# pico.net
KiCad netlist of a schematic drawn in EAGLE
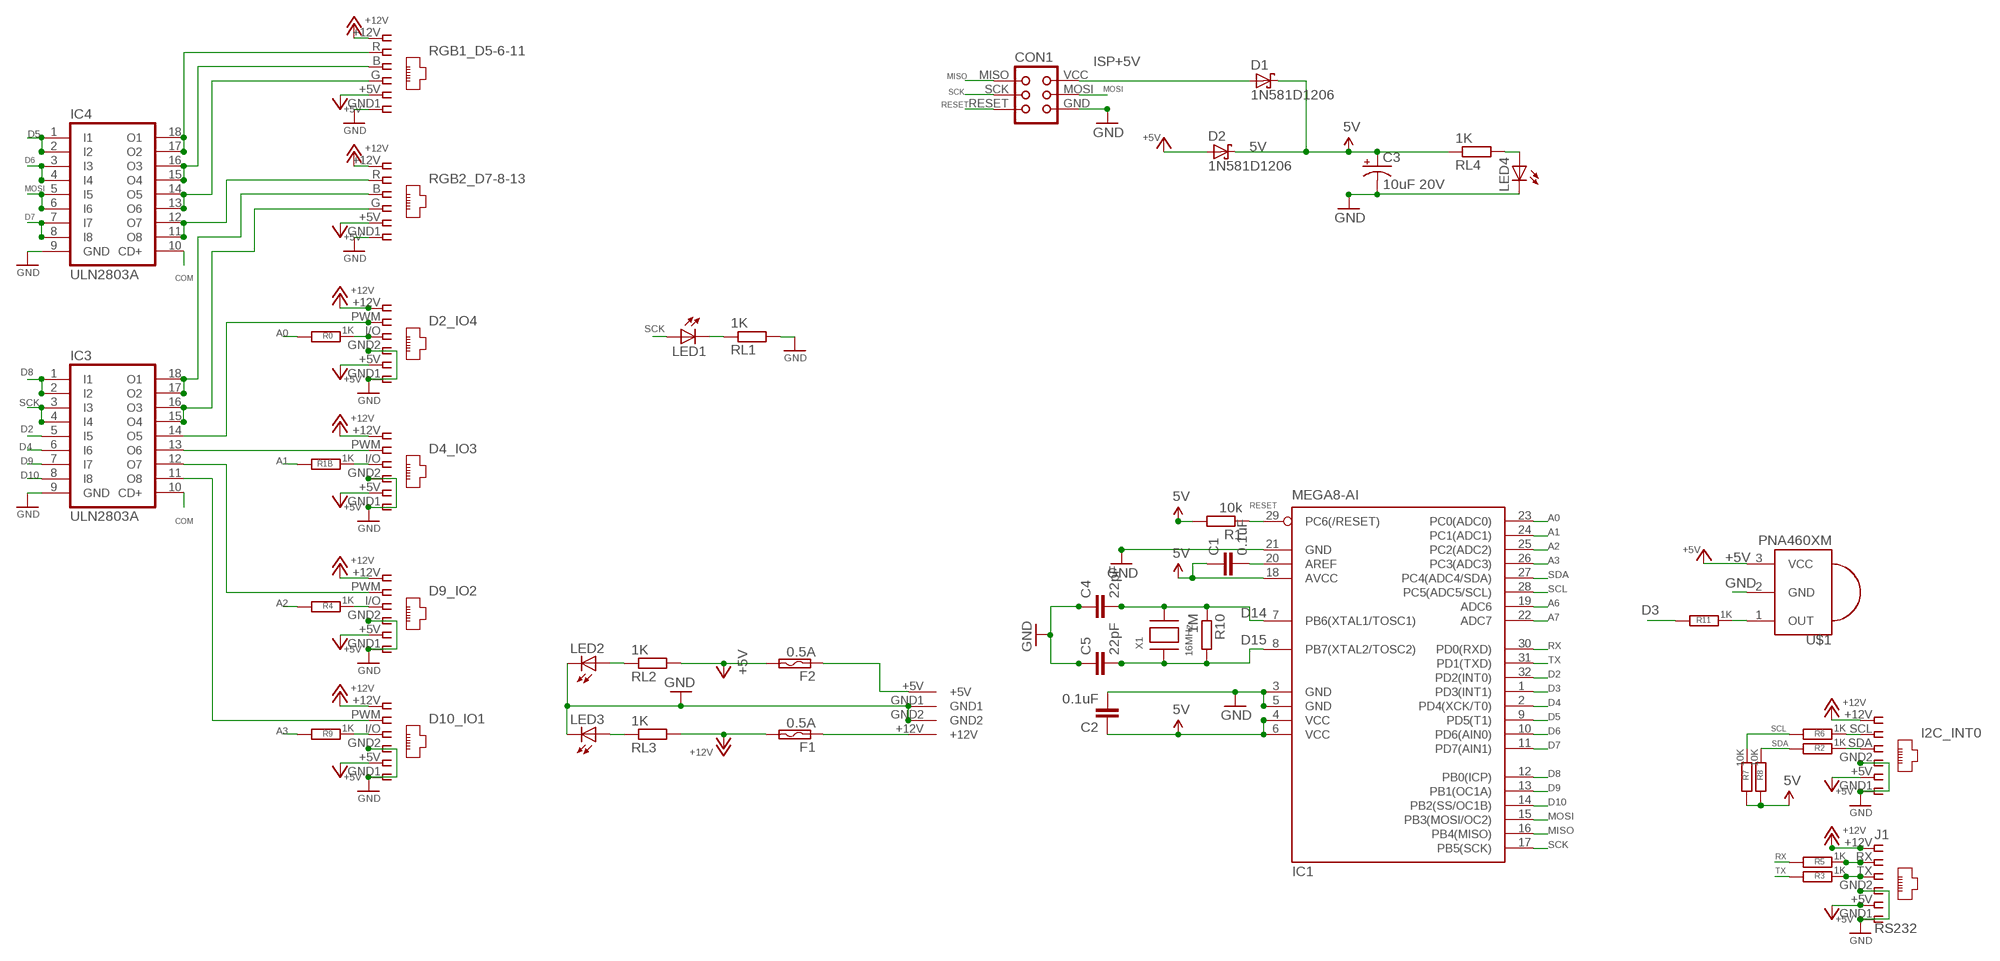
[diagram p0: schematic, sheet 1]

(export (version "E")
  (design (tool "Eeschema 10.0.6"))
  (components
    (comp (ref "C1")
      (value "0.1uF")
      (footprint "eagle-import:C1206")
      (libsource (lib "eagle-import") (part "C-EUC1206"))
    )
    (comp (ref "C2")
      (value "0.1uF")
      (footprint "eagle-import:C1206")
      (libsource (lib "eagle-import") (part "C-EUC1206"))
    )
    (comp (ref "C3")
      (value "10uF 20V")
      (footprint "eagle-import:EIA3216-KIT")
      (libsource (lib "eagle-import") (part "CAP_POL1206-KIT"))
    )
    (comp (ref "C4")
      (value "22pF")
      (footprint "eagle-import:C1206")
      (libsource (lib "eagle-import") (part "C-EUC1206"))
    )
    (comp (ref "C5")
      (value "22pF")
      (footprint "eagle-import:C1206")
      (libsource (lib "eagle-import") (part "C-EUC1206"))
    )
    (comp (ref "CON1")
      (value "TINYISP")
      (footprint "eagle-import:TINYISP")
      (libsource (lib "eagle-import") (part "TINYISP"))
    )
    (comp (ref "D1")
      (value "1N581D1206")
      (footprint "eagle-import:LED-1206")
      (libsource (lib "eagle-import") (part "1N581D1206"))
    )
    (comp (ref "D2")
      (value "1N581D1206")
      (footprint "eagle-import:LED-1206")
      (libsource (lib "eagle-import") (part "1N581D1206"))
    )
    (comp (ref "D2_IO4")
      (value "IO4")
      (footprint "eagle-import:RJ12-STRAIGHT")
      (libsource (lib "eagle-import") (part "RJ12STRAIGHT"))
    )
    (comp (ref "D4_IO3")
      (value "IO3")
      (footprint "eagle-import:RJ12-STRAIGHT")
      (libsource (lib "eagle-import") (part "RJ12STRAIGHT"))
    )
    (comp (ref "D9_IO2")
      (value "IO2")
      (footprint "eagle-import:RJ12-STRAIGHT")
      (libsource (lib "eagle-import") (part "RJ12STRAIGHT"))
    )
    (comp (ref "D10_IO1")
      (value "IO1")
      (footprint "eagle-import:RJ12-STRAIGHT")
      (libsource (lib "eagle-import") (part "RJ12STRAIGHT"))
    )
    (comp (ref "F1")
      (value "0.5A")
      (footprint "eagle-import:C1812")
      (libsource (lib "eagle-import") (part "POLYSWITCHSMD1812"))
    )
    (comp (ref "F2")
      (value "0.5A")
      (footprint "eagle-import:C1812")
      (libsource (lib "eagle-import") (part "POLYSWITCHSMD1812"))
    )
    (comp (ref "I2C_INT0")
      (value "I2C")
      (footprint "eagle-import:RJ12-STRAIGHT-I2C")
      (libsource (lib "eagle-import") (part "RJ12STRAIGHT-I2C"))
    )
    (comp (ref "IC1")
      (value "MEGA8-AI")
      (footprint "eagle-import:TQFP32-08")
      (fields (field (name "MPN") "ATMEGA8-16AU"))
      (libsource (lib "eagle-import") (part "MEGA8-AI"))
    )
    (comp (ref "IC3")
      (value "ULN2803A")
      (footprint "eagle-import:SO18W")
      (libsource (lib "eagle-import") (part "ULN2803A"))
    )
    (comp (ref "IC4")
      (value "ULN2803A")
      (footprint "eagle-import:SO18W")
      (libsource (lib "eagle-import") (part "ULN2803A"))
    )
    (comp (ref "J1")
      (value "RS232")
      (footprint "eagle-import:RJ12-STRAIGHT-RS232")
      (libsource (lib "eagle-import") (part "RJ12STRAIGHT-RS232-SERVER"))
    )
    (comp (ref "LED1")
      (value "LED3MM")
      (footprint "eagle-import:LED3MM")
      (libsource (lib "eagle-import") (part "LED3MM"))
    )
    (comp (ref "LED2")
      (value "LED3MM")
      (footprint "eagle-import:LED3MM")
      (libsource (lib "eagle-import") (part "LED3MM"))
    )
    (comp (ref "LED3")
      (value "LED3MM")
      (footprint "eagle-import:LED3MM")
      (libsource (lib "eagle-import") (part "LED3MM"))
    )
    (comp (ref "LED4")
      (value "LED3MM")
      (footprint "eagle-import:LED3MM")
      (libsource (lib "eagle-import") (part "LED3MM"))
    )
    (comp (ref "R0")
      (value "1K")
      (footprint "eagle-import:M1206")
      (libsource (lib "eagle-import") (part "R-EU_M1206"))
    )
    (comp (ref "R1")
      (value "10k")
      (footprint "eagle-import:M1206")
      (libsource (lib "eagle-import") (part "R-EU_M1206"))
    )
    (comp (ref "R1B")
      (value "1K")
      (footprint "eagle-import:M1206")
      (libsource (lib "eagle-import") (part "R-EU_M1206"))
    )
    (comp (ref "R2")
      (value "1K")
      (footprint "eagle-import:M1206")
      (libsource (lib "eagle-import") (part "R-EU_M1206"))
    )
    (comp (ref "R3")
      (value "1K")
      (footprint "eagle-import:M1206")
      (libsource (lib "eagle-import") (part "R-EU_M1206"))
    )
    (comp (ref "R4")
      (value "1K")
      (footprint "eagle-import:M1206")
      (libsource (lib "eagle-import") (part "R-EU_M1206"))
    )
    (comp (ref "R5")
      (value "1K")
      (footprint "eagle-import:M1206")
      (libsource (lib "eagle-import") (part "R-EU_M1206"))
    )
    (comp (ref "R6")
      (value "1K")
      (footprint "eagle-import:M1206")
      (libsource (lib "eagle-import") (part "R-EU_M1206"))
    )
    (comp (ref "R7")
      (value "10K")
      (footprint "eagle-import:M1206")
      (libsource (lib "eagle-import") (part "R-EU_M1206"))
    )
    (comp (ref "R8")
      (value "10K")
      (footprint "eagle-import:M1206")
      (libsource (lib "eagle-import") (part "R-EU_M1206"))
    )
    (comp (ref "R9")
      (value "1K")
      (footprint "eagle-import:M1206")
      (libsource (lib "eagle-import") (part "R-EU_M1206"))
    )
    (comp (ref "R10")
      (value "1M")
      (footprint "eagle-import:M1206")
      (libsource (lib "eagle-import") (part "R-EU_M1206"))
    )
    (comp (ref "R11")
      (value "1K")
      (footprint "eagle-import:M1206")
      (libsource (lib "eagle-import") (part "R-EU_M1206"))
    )
    (comp (ref "RGB1_D5-6-11")
      (value "RGB1")
      (footprint "eagle-import:RJ12-STRAIGHT-RGB")
      (libsource (lib "eagle-import") (part "RJ12STRAIGHT-RGB"))
    )
    (comp (ref "RGB2_D7-8-13")
      (value "RGB2")
      (footprint "eagle-import:RJ12-STRAIGHT-RGB")
      (libsource (lib "eagle-import") (part "RJ12STRAIGHT-RGB"))
    )
    (comp (ref "RL1")
      (value "1K")
      (footprint "eagle-import:M1206")
      (libsource (lib "eagle-import") (part "R-EU_M1206"))
    )
    (comp (ref "RL2")
      (value "1K")
      (footprint "eagle-import:M1206")
      (libsource (lib "eagle-import") (part "R-EU_M1206"))
    )
    (comp (ref "RL3")
      (value "1K")
      (footprint "eagle-import:M1206")
      (libsource (lib "eagle-import") (part "R-EU_M1206"))
    )
    (comp (ref "RL4")
      (value "1K")
      (footprint "eagle-import:M1206")
      (libsource (lib "eagle-import") (part "R-EU_M1206"))
    )
    (comp (ref "U$1")
      (value "PNA460XM")
      (footprint "eagle-import:PNA460XM")
      (libsource (lib "eagle-import") (part "PNA460XM"))
    )
    (comp (ref "U$2")
      (value "KPJX-4S-S")
      (footprint "eagle-import:KPJX-4S-S")
      (libsource (lib "eagle-import") (part "KPJX-4S-S"))
    )
    (comp (ref "X1")
      (value "16MHz")
      (footprint "eagle-import:NX6035")
      (libsource (lib "eagle-import") (part "XTALNX6035"))
    )
  )
  (nets
    (net (code "1") (name "+5V") (class "Default")
      (node (ref "D10_IO1") (pin "+5V") (pinfunction "5_+5V") (pintype "power_in"))
      (node (ref "D2") (pin "A") (pinfunction "A_A") (pintype "passive"))
      (node (ref "D2_IO4") (pin "+5V") (pinfunction "5_+5V") (pintype "power_in"))
      (node (ref "D4_IO3") (pin "+5V") (pinfunction "5_+5V") (pintype "power_in"))
      (node (ref "D9_IO2") (pin "+5V") (pinfunction "5_+5V") (pintype "power_in"))
      (node (ref "F2") (pin "2") (pinfunction "2_2") (pintype "passive"))
      (node (ref "I2C_INT0") (pin "+5V") (pinfunction "5_+5V") (pintype "power_in"))
      (node (ref "J1") (pin "+5V") (pinfunction "5_+5V") (pintype "power_in"))
      (node (ref "RGB1_D5-6-11") (pin "+5V") (pinfunction "5_+5V") (pintype "power_in"))
      (node (ref "RGB2_D7-8-13") (pin "+5V") (pinfunction "5_+5V") (pintype "power_in"))
      (node (ref "RL2") (pin "2") (pinfunction "2_2") (pintype "passive"))
      (node (ref "U$1") (pin "3") (pinfunction "VCC_3") (pintype "power_in"))
    )
    (net (code "2") (name "+12V") (class "Default")
      (node (ref "D10_IO1") (pin "+12V") (pinfunction "1_+12V") (pintype "power_in"))
      (node (ref "D2_IO4") (pin "+12V") (pinfunction "1_+12V") (pintype "power_in"))
      (node (ref "D4_IO3") (pin "+12V") (pinfunction "1_+12V") (pintype "power_in"))
      (node (ref "D9_IO2") (pin "+12V") (pinfunction "1_+12V") (pintype "power_in"))
      (node (ref "F1") (pin "2") (pinfunction "2_2") (pintype "passive"))
      (node (ref "I2C_INT0") (pin "+12V") (pinfunction "1_+12V") (pintype "power_in"))
      (node (ref "J1") (pin "+12V") (pinfunction "1_+12V") (pintype "power_in"))
      (node (ref "RGB1_D5-6-11") (pin "+12V") (pinfunction "1_+12V") (pintype "power_in"))
      (node (ref "RGB2_D7-8-13") (pin "+12V") (pinfunction "1_+12V") (pintype "power_in"))
      (node (ref "RL3") (pin "2") (pinfunction "2_2") (pintype "passive"))
    )
    (net (code "3") (name "/A0") (class "Default")
      (node (ref "IC1") (pin "23") (pinfunction "PC0(ADC0)_23") (pintype "bidirectional"))
      (node (ref "R0") (pin "2") (pinfunction "2_2") (pintype "passive"))
    )
    (net (code "4") (name "/A1") (class "Default")
      (node (ref "IC1") (pin "24") (pinfunction "PC1(ADC1)_24") (pintype "bidirectional"))
      (node (ref "R1B") (pin "2") (pinfunction "2_2") (pintype "passive"))
    )
    (net (code "5") (name "/A2") (class "Default")
      (node (ref "IC1") (pin "25") (pinfunction "PC2(ADC2)_25") (pintype "bidirectional"))
      (node (ref "R4") (pin "2") (pinfunction "2_2") (pintype "passive"))
    )
    (net (code "6") (name "/A3") (class "Default")
      (node (ref "IC1") (pin "26") (pinfunction "PC3(ADC3)_26") (pintype "bidirectional"))
      (node (ref "R9") (pin "2") (pinfunction "2_2") (pintype "passive"))
    )
    (net (code "7") (name "/A6") (class "Default")
      (node (ref "IC1") (pin "19") (pinfunction "ADC6_19") (pintype "bidirectional"))
    )
    (net (code "8") (name "/A7") (class "Default")
      (node (ref "IC1") (pin "22") (pinfunction "ADC7_22") (pintype "bidirectional"))
    )
    (net (code "9") (name "/COM") (class "Default")
      (node (ref "IC3") (pin "10") (pinfunction "CD+_10") (pintype "passive"))
      (node (ref "IC4") (pin "10") (pinfunction "CD+_10") (pintype "passive"))
    )
    (net (code "10") (name "/D2") (class "Default")
      (node (ref "IC1") (pin "32") (pinfunction "PD2(INT0)_32") (pintype "bidirectional"))
      (node (ref "IC3") (pin "5") (pinfunction "I5_5") (pintype "input"))
    )
    (net (code "11") (name "/D3") (class "Default")
      (node (ref "IC1") (pin "1") (pinfunction "PD3(INT1)_1") (pintype "bidirectional"))
      (node (ref "R11") (pin "2") (pinfunction "2_2") (pintype "passive"))
    )
    (net (code "12") (name "/D4") (class "Default")
      (node (ref "IC1") (pin "2") (pinfunction "PD4(XCK/T0)_2") (pintype "bidirectional"))
      (node (ref "IC3") (pin "6") (pinfunction "I6_6") (pintype "input"))
    )
    (net (code "13") (name "/D5") (class "Default")
      (node (ref "IC1") (pin "9") (pinfunction "PD5(T1)_9") (pintype "bidirectional"))
      (node (ref "IC4") (pin "1") (pinfunction "I1_1") (pintype "input"))
      (node (ref "IC4") (pin "2") (pinfunction "I2_2") (pintype "input"))
    )
    (net (code "14") (name "/D6") (class "Default")
      (node (ref "IC1") (pin "10") (pinfunction "PD6(AIN0)_10") (pintype "bidirectional"))
      (node (ref "IC4") (pin "3") (pinfunction "I3_3") (pintype "input"))
      (node (ref "IC4") (pin "4") (pinfunction "I4_4") (pintype "input"))
    )
    (net (code "15") (name "/D7") (class "Default")
      (node (ref "IC1") (pin "11") (pinfunction "PD7(AIN1)_11") (pintype "bidirectional"))
      (node (ref "IC4") (pin "7") (pinfunction "I7_7") (pintype "input"))
      (node (ref "IC4") (pin "8") (pinfunction "I8_8") (pintype "input"))
    )
    (net (code "16") (name "/D8") (class "Default")
      (node (ref "IC1") (pin "12") (pinfunction "PB0(ICP)_12") (pintype "bidirectional"))
      (node (ref "IC3") (pin "1") (pinfunction "I1_1") (pintype "input"))
      (node (ref "IC3") (pin "2") (pinfunction "I2_2") (pintype "input"))
    )
    (net (code "17") (name "/D9") (class "Default")
      (node (ref "IC1") (pin "13") (pinfunction "PB1(OC1A)_13") (pintype "bidirectional"))
      (node (ref "IC3") (pin "7") (pinfunction "I7_7") (pintype "input"))
    )
    (net (code "18") (name "/D10") (class "Default")
      (node (ref "IC1") (pin "14") (pinfunction "PB2(SS/OC1B)_14") (pintype "bidirectional"))
      (node (ref "IC3") (pin "8") (pinfunction "I8_8") (pintype "input"))
    )
    (net (code "19") (name "/D14") (class "Default")
      (node (ref "C4") (pin "2") (pinfunction "2_2") (pintype "passive"))
      (node (ref "IC1") (pin "7") (pinfunction "PB6(XTAL1/TOSC1)_7") (pintype "bidirectional"))
      (node (ref "R10") (pin "1") (pinfunction "1_1") (pintype "passive"))
      (node (ref "X1") (pin "P$2") (pinfunction "P$2_P$2") (pintype "bidirectional"))
    )
    (net (code "20") (name "/D15") (class "Default")
      (node (ref "C5") (pin "2") (pinfunction "2_2") (pintype "passive"))
      (node (ref "IC1") (pin "8") (pinfunction "PB7(XTAL2/TOSC2)_8") (pintype "bidirectional"))
      (node (ref "R10") (pin "2") (pinfunction "2_2") (pintype "passive"))
      (node (ref "X1") (pin "P$1") (pinfunction "P$1_P$1") (pintype "bidirectional"))
    )
    (net (code "21") (name "/ISP+5V") (class "Default")
      (node (ref "CON1") (pin "VCC") (pinfunction "VCC_VCC") (pintype "passive"))
      (node (ref "D1") (pin "A") (pinfunction "A_A") (pintype "passive"))
    )
    (net (code "22") (name "/MISO") (class "Default")
      (node (ref "CON1") (pin "MISO") (pinfunction "MISO_MISO") (pintype "passive"))
      (node (ref "IC1") (pin "16") (pinfunction "PB4(MISO)_16") (pintype "bidirectional"))
    )
    (net (code "23") (name "/MOSI") (class "Default")
      (node (ref "CON1") (pin "MOSI") (pinfunction "MOSI_MOSI") (pintype "passive"))
      (node (ref "IC1") (pin "15") (pinfunction "PB3(MOSI/OC2)_15") (pintype "bidirectional"))
      (node (ref "IC4") (pin "5") (pinfunction "I5_5") (pintype "input"))
      (node (ref "IC4") (pin "6") (pinfunction "I6_6") (pintype "input"))
    )
    (net (code "24") (name "/RESET") (class "Default")
      (node (ref "CON1") (pin "RESET") (pinfunction "RESET_RESET") (pintype "passive"))
      (node (ref "IC1") (pin "29") (pinfunction "PC6(/RESET)_29") (pintype "bidirectional"))
      (node (ref "R1") (pin "1") (pinfunction "1_1") (pintype "passive"))
    )
    (net (code "25") (name "/RX") (class "Default")
      (node (ref "IC1") (pin "30") (pinfunction "PD0(RXD)_30") (pintype "bidirectional"))
      (node (ref "R5") (pin "2") (pinfunction "2_2") (pintype "passive"))
    )
    (net (code "26") (name "/SCK") (class "Default")
      (node (ref "CON1") (pin "SCK") (pinfunction "SCK_SCK") (pintype "passive"))
      (node (ref "IC1") (pin "17") (pinfunction "PB5(SCK)_17") (pintype "bidirectional"))
      (node (ref "IC3") (pin "3") (pinfunction "I3_3") (pintype "input"))
      (node (ref "IC3") (pin "4") (pinfunction "I4_4") (pintype "input"))
      (node (ref "LED1") (pin "A") (pinfunction "A_A") (pintype "passive"))
    )
    (net (code "27") (name "/SCL") (class "Default")
      (node (ref "IC1") (pin "28") (pinfunction "PC5(ADC5/SCL)_28") (pintype "bidirectional"))
      (node (ref "R6") (pin "2") (pinfunction "2_2") (pintype "passive"))
      (node (ref "R7") (pin "1") (pinfunction "1_1") (pintype "passive"))
    )
    (net (code "28") (name "/SDA") (class "Default")
      (node (ref "IC1") (pin "27") (pinfunction "PC4(ADC4/SDA)_27") (pintype "bidirectional"))
      (node (ref "R2") (pin "2") (pinfunction "2_2") (pintype "passive"))
      (node (ref "R8") (pin "1") (pinfunction "1_1") (pintype "passive"))
    )
    (net (code "29") (name "/TX") (class "Default")
      (node (ref "IC1") (pin "31") (pinfunction "PD1(TXD)_31") (pintype "bidirectional"))
      (node (ref "R3") (pin "2") (pinfunction "2_2") (pintype "passive"))
    )
    (net (code "30") (name "5V") (class "Default")
      (node (ref "C1") (pin "1") (pinfunction "1_1") (pintype "passive"))
      (node (ref "C2") (pin "1") (pinfunction "1_1") (pintype "passive"))
      (node (ref "C3") (pin "A") (pinfunction "+_A") (pintype "passive"))
      (node (ref "D1") (pin "C") (pinfunction "C_C") (pintype "passive"))
      (node (ref "D2") (pin "C") (pinfunction "C_C") (pintype "passive"))
      (node (ref "IC1") (pin "18") (pinfunction "AVCC_18") (pintype "power_in"))
      (node (ref "IC1") (pin "4") (pinfunction "VCC_4") (pintype "power_in"))
      (node (ref "IC1") (pin "6") (pinfunction "VCC_6") (pintype "power_in"))
      (node (ref "R1") (pin "2") (pinfunction "2_2") (pintype "passive"))
      (node (ref "R7") (pin "2") (pinfunction "2_2") (pintype "passive"))
      (node (ref "R8") (pin "2") (pinfunction "2_2") (pintype "passive"))
      (node (ref "RL4") (pin "1") (pinfunction "1_1") (pintype "passive"))
    )
    (net (code "31") (name "GND") (class "Default")
      (node (ref "C2") (pin "2") (pinfunction "2_2") (pintype "passive"))
      (node (ref "C3") (pin "C") (pinfunction "-_C") (pintype "passive"))
      (node (ref "C4") (pin "1") (pinfunction "1_1") (pintype "passive"))
      (node (ref "C5") (pin "1") (pinfunction "1_1") (pintype "passive"))
      (node (ref "CON1") (pin "GND") (pinfunction "GND_GND") (pintype "passive"))
      (node (ref "D10_IO1") (pin "GND1") (pinfunction "6_GND1") (pintype "power_in"))
      (node (ref "D10_IO1") (pin "GND2") (pinfunction "4_GND2") (pintype "power_in"))
      (node (ref "D2_IO4") (pin "GND1") (pinfunction "6_GND1") (pintype "power_in"))
      (node (ref "D2_IO4") (pin "GND2") (pinfunction "4_GND2") (pintype "power_in"))
      (node (ref "D4_IO3") (pin "GND1") (pinfunction "6_GND1") (pintype "power_in"))
      (node (ref "D4_IO3") (pin "GND2") (pinfunction "4_GND2") (pintype "power_in"))
      (node (ref "D9_IO2") (pin "GND1") (pinfunction "6_GND1") (pintype "power_in"))
      (node (ref "D9_IO2") (pin "GND2") (pinfunction "4_GND2") (pintype "power_in"))
      (node (ref "I2C_INT0") (pin "GND1") (pinfunction "6_GND1") (pintype "power_in"))
      (node (ref "I2C_INT0") (pin "GND2") (pinfunction "4_GND2") (pintype "power_in"))
      (node (ref "IC1") (pin "21") (pinfunction "GND_21") (pintype "power_in"))
      (node (ref "IC1") (pin "3") (pinfunction "GND_3") (pintype "power_in"))
      (node (ref "IC1") (pin "5") (pinfunction "GND_5") (pintype "power_in"))
      (node (ref "IC3") (pin "9") (pinfunction "GND_9") (pintype "power_in"))
      (node (ref "IC4") (pin "9") (pinfunction "GND_9") (pintype "power_in"))
      (node (ref "J1") (pin "GND1") (pinfunction "6_GND1") (pintype "power_in"))
      (node (ref "J1") (pin "GND2") (pinfunction "4_GND2") (pintype "power_in"))
      (node (ref "LED2") (pin "K") (pinfunction "C_K") (pintype "passive"))
      (node (ref "LED3") (pin "K") (pinfunction "C_K") (pintype "passive"))
      (node (ref "LED4") (pin "K") (pinfunction "C_K") (pintype "passive"))
      (node (ref "RGB1_D5-6-11") (pin "GND1") (pinfunction "6_GND1") (pintype "power_in"))
      (node (ref "RGB2_D7-8-13") (pin "GND1") (pinfunction "6_GND1") (pintype "power_in"))
      (node (ref "RL1") (pin "2") (pinfunction "2_2") (pintype "passive"))
      (node (ref "U$1") (pin "2") (pinfunction "GND_2") (pintype "power_in"))
      (node (ref "U$2") (pin "GND1") (pinfunction "GND1_GND1") (pintype "input"))
      (node (ref "U$2") (pin "GND2") (pinfunction "GND2_GND2") (pintype "input"))
    )
    (net (code "32") (name "Net-(D2_IO4-2)") (class "Default")
      (node (ref "D2_IO4") (pin "PWM") (pinfunction "2_PWM") (pintype "bidirectional"))
      (node (ref "IC3") (pin "14") (pinfunction "O5_14") (pintype "open_collector"))
    )
    (net (code "33") (name "Net-(D2_IO4-3)") (class "Default")
      (node (ref "D2_IO4") (pin "I/O") (pinfunction "3_I/O") (pintype "bidirectional"))
      (node (ref "R0") (pin "1") (pinfunction "1_1") (pintype "passive"))
    )
    (net (code "34") (name "Net-(D4_IO3-2)") (class "Default")
      (node (ref "D4_IO3") (pin "PWM") (pinfunction "2_PWM") (pintype "bidirectional"))
      (node (ref "IC3") (pin "13") (pinfunction "O6_13") (pintype "open_collector"))
    )
    (net (code "35") (name "Net-(D4_IO3-3)") (class "Default")
      (node (ref "D4_IO3") (pin "I/O") (pinfunction "3_I/O") (pintype "bidirectional"))
      (node (ref "R1B") (pin "1") (pinfunction "1_1") (pintype "passive"))
    )
    (net (code "36") (name "Net-(D9_IO2-2)") (class "Default")
      (node (ref "D9_IO2") (pin "PWM") (pinfunction "2_PWM") (pintype "bidirectional"))
      (node (ref "IC3") (pin "12") (pinfunction "O7_12") (pintype "open_collector"))
    )
    (net (code "37") (name "Net-(D9_IO2-3)") (class "Default")
      (node (ref "D9_IO2") (pin "I/O") (pinfunction "3_I/O") (pintype "bidirectional"))
      (node (ref "R4") (pin "1") (pinfunction "1_1") (pintype "passive"))
    )
    (net (code "38") (name "Net-(D10_IO1-2)") (class "Default")
      (node (ref "D10_IO1") (pin "PWM") (pinfunction "2_PWM") (pintype "bidirectional"))
      (node (ref "IC3") (pin "11") (pinfunction "O8_11") (pintype "open_collector"))
    )
    (net (code "39") (name "Net-(D10_IO1-3)") (class "Default")
      (node (ref "D10_IO1") (pin "I/O") (pinfunction "3_I/O") (pintype "bidirectional"))
      (node (ref "R9") (pin "1") (pinfunction "1_1") (pintype "passive"))
    )
    (net (code "40") (name "Net-(F1-Pad1)") (class "Default")
      (node (ref "F1") (pin "1") (pinfunction "1_1") (pintype "passive"))
      (node (ref "U$2") (pin "+12V") (pinfunction "+12V_+12V") (pintype "power_in"))
    )
    (net (code "41") (name "Net-(F2-Pad1)") (class "Default")
      (node (ref "F2") (pin "1") (pinfunction "1_1") (pintype "passive"))
      (node (ref "U$2") (pin "+5V") (pinfunction "+5V_+5V") (pintype "power_in"))
    )
    (net (code "42") (name "Net-(I2C_INT0-2)") (class "Default")
      (node (ref "I2C_INT0") (pin "SCL") (pinfunction "2_SCL") (pintype "bidirectional"))
      (node (ref "R6") (pin "1") (pinfunction "1_1") (pintype "passive"))
    )
    (net (code "43") (name "Net-(I2C_INT0-3)") (class "Default")
      (node (ref "I2C_INT0") (pin "SDA") (pinfunction "3_SDA") (pintype "bidirectional"))
      (node (ref "R2") (pin "1") (pinfunction "1_1") (pintype "passive"))
    )
    (net (code "44") (name "Net-(IC1-AREF)") (class "Default")
      (node (ref "C1") (pin "2") (pinfunction "2_2") (pintype "passive"))
      (node (ref "IC1") (pin "20") (pinfunction "AREF_20") (pintype "passive"))
    )
    (net (code "45") (name "Net-(IC3-O1)") (class "Default")
      (node (ref "IC3") (pin "17") (pinfunction "O2_17") (pintype "open_collector"))
      (node (ref "IC3") (pin "18") (pinfunction "O1_18") (pintype "open_collector"))
      (node (ref "RGB2_D7-8-13") (pin "B") (pinfunction "3_B") (pintype "bidirectional"))
    )
    (net (code "46") (name "Net-(IC3-O3)") (class "Default")
      (node (ref "IC3") (pin "15") (pinfunction "O4_15") (pintype "open_collector"))
      (node (ref "IC3") (pin "16") (pinfunction "O3_16") (pintype "open_collector"))
      (node (ref "RGB2_D7-8-13") (pin "G") (pinfunction "4_G") (pintype "power_in"))
    )
    (net (code "47") (name "Net-(IC4-O1)") (class "Default")
      (node (ref "IC4") (pin "17") (pinfunction "O2_17") (pintype "open_collector"))
      (node (ref "IC4") (pin "18") (pinfunction "O1_18") (pintype "open_collector"))
      (node (ref "RGB1_D5-6-11") (pin "R") (pinfunction "2_R") (pintype "bidirectional"))
    )
    (net (code "48") (name "Net-(IC4-O3)") (class "Default")
      (node (ref "IC4") (pin "15") (pinfunction "O4_15") (pintype "open_collector"))
      (node (ref "IC4") (pin "16") (pinfunction "O3_16") (pintype "open_collector"))
      (node (ref "RGB1_D5-6-11") (pin "B") (pinfunction "3_B") (pintype "bidirectional"))
    )
    (net (code "49") (name "Net-(IC4-O5)") (class "Default")
      (node (ref "IC4") (pin "13") (pinfunction "O6_13") (pintype "open_collector"))
      (node (ref "IC4") (pin "14") (pinfunction "O5_14") (pintype "open_collector"))
      (node (ref "RGB1_D5-6-11") (pin "G") (pinfunction "4_G") (pintype "power_in"))
    )
    (net (code "50") (name "Net-(IC4-O7)") (class "Default")
      (node (ref "IC4") (pin "11") (pinfunction "O8_11") (pintype "open_collector"))
      (node (ref "IC4") (pin "12") (pinfunction "O7_12") (pintype "open_collector"))
      (node (ref "RGB2_D7-8-13") (pin "R") (pinfunction "2_R") (pintype "bidirectional"))
    )
    (net (code "51") (name "Net-(J1-2)") (class "Default")
      (node (ref "J1") (pin "RX") (pinfunction "2_RX") (pintype "bidirectional"))
      (node (ref "R5") (pin "1") (pinfunction "1_1") (pintype "passive"))
    )
    (net (code "52") (name "Net-(J1-3)") (class "Default")
      (node (ref "J1") (pin "TX") (pinfunction "3_TX") (pintype "bidirectional"))
      (node (ref "R3") (pin "1") (pinfunction "1_1") (pintype "passive"))
    )
    (net (code "53") (name "Net-(LED1-C)") (class "Default")
      (node (ref "LED1") (pin "K") (pinfunction "C_K") (pintype "passive"))
      (node (ref "RL1") (pin "1") (pinfunction "1_1") (pintype "passive"))
    )
    (net (code "54") (name "Net-(LED2-PadA)") (class "Default")
      (node (ref "LED2") (pin "A") (pinfunction "A_A") (pintype "passive"))
      (node (ref "RL2") (pin "1") (pinfunction "1_1") (pintype "passive"))
    )
    (net (code "55") (name "Net-(LED3-PadA)") (class "Default")
      (node (ref "LED3") (pin "A") (pinfunction "A_A") (pintype "passive"))
      (node (ref "RL3") (pin "1") (pinfunction "1_1") (pintype "passive"))
    )
    (net (code "56") (name "Net-(LED4-PadA)") (class "Default")
      (node (ref "LED4") (pin "A") (pinfunction "A_A") (pintype "passive"))
      (node (ref "RL4") (pin "2") (pinfunction "2_2") (pintype "passive"))
    )
    (net (code "57") (name "Net-(U$1-OUT)") (class "Default")
      (node (ref "R11") (pin "1") (pinfunction "1_1") (pintype "passive"))
      (node (ref "U$1") (pin "1") (pinfunction "OUT_1") (pintype "output"))
    )
  )
)
